# schema.net
KiCad netlist of a schematic drawn in EAGLE
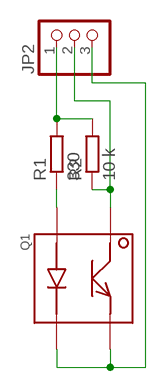
[diagram p0: schematic, sheet 1]

(export (version "E")
  (design (tool "Eeschema 10.0.6"))
  (components
    (comp (ref "JP2")
      (value "PINHD-1X3")
      (footprint "eagle-import:1X03")
      (libsource (lib "eagle-import") (part "PINHD-1X3"))
    )
    (comp (ref "Q1")
      (value "QRD1114")
      (footprint "eagle-import:QRD1114")
      (fields (field (name "MF") "ON Semiconductor"))
      (libsource (lib "eagle-import") (part "QRD1114"))
    )
    (comp (ref "R1")
      (value "330")
      (footprint "eagle-import:MINI_MELF-0102W")
      (libsource (lib "eagle-import") (part "R-EU_MELF0102W"))
    )
    (comp (ref "R2")
      (value "10 k")
      (footprint "eagle-import:MINI_MELF-0102W")
      (libsource (lib "eagle-import") (part "R-EU_MELF0102W"))
    )
  )
  (nets
    (net (code "1") (name "Net-(JP2-Pad1)") (class "Default")
      (node (ref "JP2") (pin "1") (pinfunction "1_1") (pintype "passive"))
      (node (ref "R1") (pin "2") (pinfunction "2_2") (pintype "passive"))
      (node (ref "R2") (pin "2") (pinfunction "2_2") (pintype "passive"))
    )
    (net (code "2") (name "Net-(JP2-Pad2)") (class "Default")
      (node (ref "JP2") (pin "2") (pinfunction "2_2") (pintype "passive"))
      (node (ref "Q1") (pin "P$1") (pinfunction "P$1_P$1") (pintype "bidirectional"))
      (node (ref "R2") (pin "1") (pinfunction "1_1") (pintype "passive"))
    )
    (net (code "3") (name "Net-(JP2-Pad3)") (class "Default")
      (node (ref "JP2") (pin "3") (pinfunction "3_3") (pintype "passive"))
      (node (ref "Q1") (pin "P$2") (pinfunction "P$2_P$2") (pintype "bidirectional"))
      (node (ref "Q1") (pin "P$4") (pinfunction "P$4_P$4") (pintype "bidirectional"))
    )
    (net (code "4") (name "Net-(Q1-PadP$3)") (class "Default")
      (node (ref "Q1") (pin "P$3") (pinfunction "P$3_P$3") (pintype "bidirectional"))
      (node (ref "R1") (pin "1") (pinfunction "1_1") (pintype "passive"))
    )
  )
)
